# RGB_LED_3.net
KiCad netlist of a schematic drawn in Altium Designer
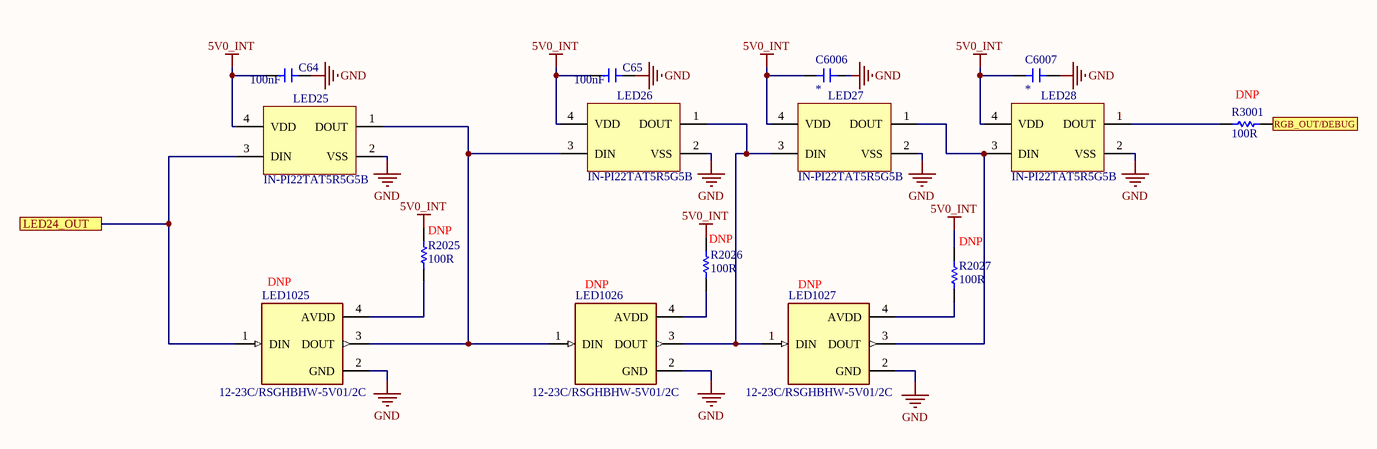
[diagram p0: RGB_LED_3.SchDoc]

(export (version "E")
  (design (tool "Eeschema 10.0.6"))
  (components
    (comp (ref "C64")
      (value "100nF")
      (footprint "MareLux24Lib:CAP_0402_CER")
      (description "100nF 0402 Ceramic Capacitor")
      (fields (field (name "PART NUMBER") "CL05B104KP5NNNC") (field (name "VOLTAGE") "10V"))
      (libsource (lib "MareLux24Lib") (part "CAP_GEN_CER"))
    )
    (comp (ref "C65")
      (value "100nF")
      (footprint "MareLux24Lib:CAP_0402_CER")
      (description "100nF 0402 Ceramic Capacitor")
      (fields (field (name "PART NUMBER") "CL05B104KP5NNNC") (field (name "VOLTAGE") "10V"))
      (libsource (lib "MareLux24Lib") (part "CAP_GEN_CER"))
    )
    (comp (ref "C6006")
      (value "*")
      (footprint "CAP_0402_CER")
      (description "Generic")
      (libsource (lib "MareLux24Lib") (part "CAP_GEN_CER"))
    )
    (comp (ref "C6007")
      (value "*")
      (footprint "CAP_0402_CER")
      (description "Generic")
      (libsource (lib "MareLux24Lib") (part "CAP_GEN_CER"))
    )
    (comp (ref "LED25")
      (value "IN-PI22TAT5R5G5B")
      (footprint "RGB_IN-PI22TAT5R5G5B")
      (description "ADDRESS LED DISCRETE SERIAL RGB")
      (fields (field (name "MANUFACTURER") "Inolux"))
      (libsource (lib "MareLux24Lib") (part "IN-PI22TAT5R5G5B"))
    )
    (comp (ref "LED26")
      (value "IN-PI22TAT5R5G5B")
      (footprint "RGB_IN-PI22TAT5R5G5B")
      (description "ADDRESS LED DISCRETE SERIAL RGB")
      (fields (field (name "MANUFACTURER") "Inolux"))
      (libsource (lib "MareLux24Lib") (part "IN-PI22TAT5R5G5B"))
    )
    (comp (ref "LED27")
      (value "IN-PI22TAT5R5G5B")
      (footprint "RGB_IN-PI22TAT5R5G5B")
      (description "ADDRESS LED DISCRETE SERIAL RGB")
      (fields (field (name "MANUFACTURER") "Inolux"))
      (libsource (lib "MareLux24Lib") (part "IN-PI22TAT5R5G5B"))
    )
    (comp (ref "LED28")
      (value "IN-PI22TAT5R5G5B")
      (footprint "RGB_IN-PI22TAT5R5G5B")
      (description "ADDRESS LED DISCRETE SERIAL RGB")
      (fields (field (name "MANUFACTURER") "Inolux"))
      (libsource (lib "MareLux24Lib") (part "IN-PI22TAT5R5G5B"))
    )
    (comp (ref "LED1025")
      (value "12-23C/RSGHBHW-5V01/2C")
      (footprint "LED_12-23C/RSGHBHW-5V01/2C")
      (fields (field (name "MF") "Everlight Electronics Co Ltd") (field (name "PLACE") "DNP"))
      (libsource (lib "12-23C_RSGHBHW-5V01_2C") (part "12-23C/RSGHBHW-5V01/2C"))
    )
    (comp (ref "LED1026")
      (value "12-23C/RSGHBHW-5V01/2C")
      (footprint "LED_12-23C/RSGHBHW-5V01/2C")
      (fields (field (name "MF") "Everlight Electronics Co Ltd") (field (name "PLACE") "DNP"))
      (libsource (lib "12-23C_RSGHBHW-5V01_2C") (part "12-23C/RSGHBHW-5V01/2C"))
    )
    (comp (ref "LED1027")
      (value "12-23C/RSGHBHW-5V01/2C")
      (footprint "LED_12-23C/RSGHBHW-5V01/2C")
      (fields (field (name "MF") "Everlight Electronics Co Ltd") (field (name "PLACE") "DNP"))
      (libsource (lib "12-23C_RSGHBHW-5V01_2C") (part "12-23C/RSGHBHW-5V01/2C"))
    )
    (comp (ref "R2025")
      (value "100R")
      (footprint "MareLux24Lib:RES_0402_SMD")
      (description "Generic Chip Res 100R")
      (fields
        (field (name "PART NUMBER") "RMCF0402JT100R")
        (field (name "TOLERANCE") "5 %")
        (field (name "PLACE") "DNP")
      )
      (libsource (lib "MareLux24Lib") (part "RES_GEN_SMD"))
    )
    (comp (ref "R2026")
      (value "100R")
      (footprint "MareLux24Lib:RES_0402_SMD")
      (description "Generic Chip Res 100R")
      (fields
        (field (name "PART NUMBER") "RMCF0402JT100R")
        (field (name "TOLERANCE") "5 %")
        (field (name "PLACE") "DNP")
      )
      (libsource (lib "MareLux24Lib") (part "RES_GEN_SMD"))
    )
    (comp (ref "R2027")
      (value "100R")
      (footprint "MareLux24Lib:RES_0402_SMD")
      (description "Generic Chip Res 100R")
      (fields
        (field (name "PART NUMBER") "RMCF0402JT100R")
        (field (name "TOLERANCE") "5 %")
        (field (name "PLACE") "DNP")
      )
      (libsource (lib "MareLux24Lib") (part "RES_GEN_SMD"))
    )
    (comp (ref "R3001")
      (value "100R")
      (footprint "RES_0402_SMD")
      (description "Generic Chip Res 100R")
      (fields
        (field (name "PART NUMBER") "RMCF0402JT100R")
        (field (name "TOLERANCE") "5 %")
        (field (name "PLACE") "DNP")
      )
      (libsource (lib "MareLux24Lib") (part "RES_GEN_SMD"))
    )
  )
  (nets
    (net (code "1") (name "/LED24_OUT") (class "Default")
      (node (ref "LED1025") (pin "1") (pinfunction "DIN_1") (pintype "input"))
      (node (ref "LED25") (pin "3") (pinfunction "DIN_3") (pintype "passive"))
    )
    (net (code "2") (name "/RGB_OUT{slash}DEBUG") (class "Default")
      (node (ref "R3001") (pin "2") (pinfunction "2_2") (pintype "passive"))
    )
    (net (code "3") (name "5V0_INT") (class "Default")
      (node (ref "C6006") (pin "1") (pinfunction "1_1") (pintype "passive"))
      (node (ref "C6007") (pin "1") (pinfunction "1_1") (pintype "passive"))
      (node (ref "C64") (pin "2") (pinfunction "2_2") (pintype "passive"))
      (node (ref "C65") (pin "2") (pinfunction "2_2") (pintype "passive"))
      (node (ref "LED25") (pin "4") (pinfunction "VDD_4") (pintype "passive"))
      (node (ref "LED26") (pin "4") (pinfunction "VDD_4") (pintype "passive"))
      (node (ref "LED27") (pin "4") (pinfunction "VDD_4") (pintype "passive"))
      (node (ref "LED28") (pin "4") (pinfunction "VDD_4") (pintype "passive"))
      (node (ref "R2025") (pin "1") (pinfunction "1_1") (pintype "passive"))
      (node (ref "R2026") (pin "1") (pinfunction "1_1") (pintype "passive"))
      (node (ref "R2027") (pin "1") (pinfunction "1_1") (pintype "passive"))
    )
    (net (code "4") (name "GND") (class "Default")
      (node (ref "C6006") (pin "2") (pinfunction "2_2") (pintype "passive"))
      (node (ref "C6007") (pin "2") (pinfunction "2_2") (pintype "passive"))
      (node (ref "C64") (pin "1") (pinfunction "1_1") (pintype "passive"))
      (node (ref "C65") (pin "1") (pinfunction "1_1") (pintype "passive"))
      (node (ref "LED1025") (pin "2") (pinfunction "GND_2") (pintype "passive"))
      (node (ref "LED1026") (pin "2") (pinfunction "GND_2") (pintype "passive"))
      (node (ref "LED1027") (pin "2") (pinfunction "GND_2") (pintype "passive"))
      (node (ref "LED25") (pin "2") (pinfunction "VSS_2") (pintype "passive"))
      (node (ref "LED26") (pin "2") (pinfunction "VSS_2") (pintype "passive"))
      (node (ref "LED27") (pin "2") (pinfunction "VSS_2") (pintype "passive"))
      (node (ref "LED28") (pin "2") (pinfunction "VSS_2") (pintype "passive"))
    )
    (net (code "5") (name "Net-(LED28-DOUT)") (class "Default")
      (node (ref "LED28") (pin "1") (pinfunction "DOUT_1") (pintype "passive"))
      (node (ref "R3001") (pin "1") (pinfunction "1_1") (pintype "passive"))
    )
    (net (code "6") (name "Net-(LED1025-AVDD)") (class "Default")
      (node (ref "LED1025") (pin "4") (pinfunction "AVDD_4") (pintype "power_in"))
      (node (ref "R2025") (pin "2") (pinfunction "2_2") (pintype "passive"))
    )
    (net (code "7") (name "Net-(LED1025-DOUT)") (class "Default")
      (node (ref "LED1025") (pin "3") (pinfunction "DOUT_3") (pintype "output"))
      (node (ref "LED1026") (pin "1") (pinfunction "DIN_1") (pintype "input"))
      (node (ref "LED25") (pin "1") (pinfunction "DOUT_1") (pintype "passive"))
      (node (ref "LED26") (pin "3") (pinfunction "DIN_3") (pintype "passive"))
    )
    (net (code "8") (name "Net-(LED1026-AVDD)") (class "Default")
      (node (ref "LED1026") (pin "4") (pinfunction "AVDD_4") (pintype "power_in"))
      (node (ref "R2026") (pin "2") (pinfunction "2_2") (pintype "passive"))
    )
    (net (code "9") (name "Net-(LED1026-DOUT)") (class "Default")
      (node (ref "LED1026") (pin "3") (pinfunction "DOUT_3") (pintype "output"))
      (node (ref "LED1027") (pin "1") (pinfunction "DIN_1") (pintype "input"))
      (node (ref "LED26") (pin "1") (pinfunction "DOUT_1") (pintype "passive"))
      (node (ref "LED27") (pin "3") (pinfunction "DIN_3") (pintype "passive"))
    )
    (net (code "10") (name "Net-(LED1027-AVDD)") (class "Default")
      (node (ref "LED1027") (pin "4") (pinfunction "AVDD_4") (pintype "power_in"))
      (node (ref "R2027") (pin "2") (pinfunction "2_2") (pintype "passive"))
    )
    (net (code "11") (name "Net-(LED1027-DOUT)") (class "Default")
      (node (ref "LED1027") (pin "3") (pinfunction "DOUT_3") (pintype "output"))
      (node (ref "LED27") (pin "1") (pinfunction "DOUT_1") (pintype "passive"))
      (node (ref "LED28") (pin "3") (pinfunction "DIN_3") (pintype "passive"))
    )
  )
)
